# Copy_of_ST_LINK_V2-1.net
KiCad netlist of a schematic drawn in Altium Designer
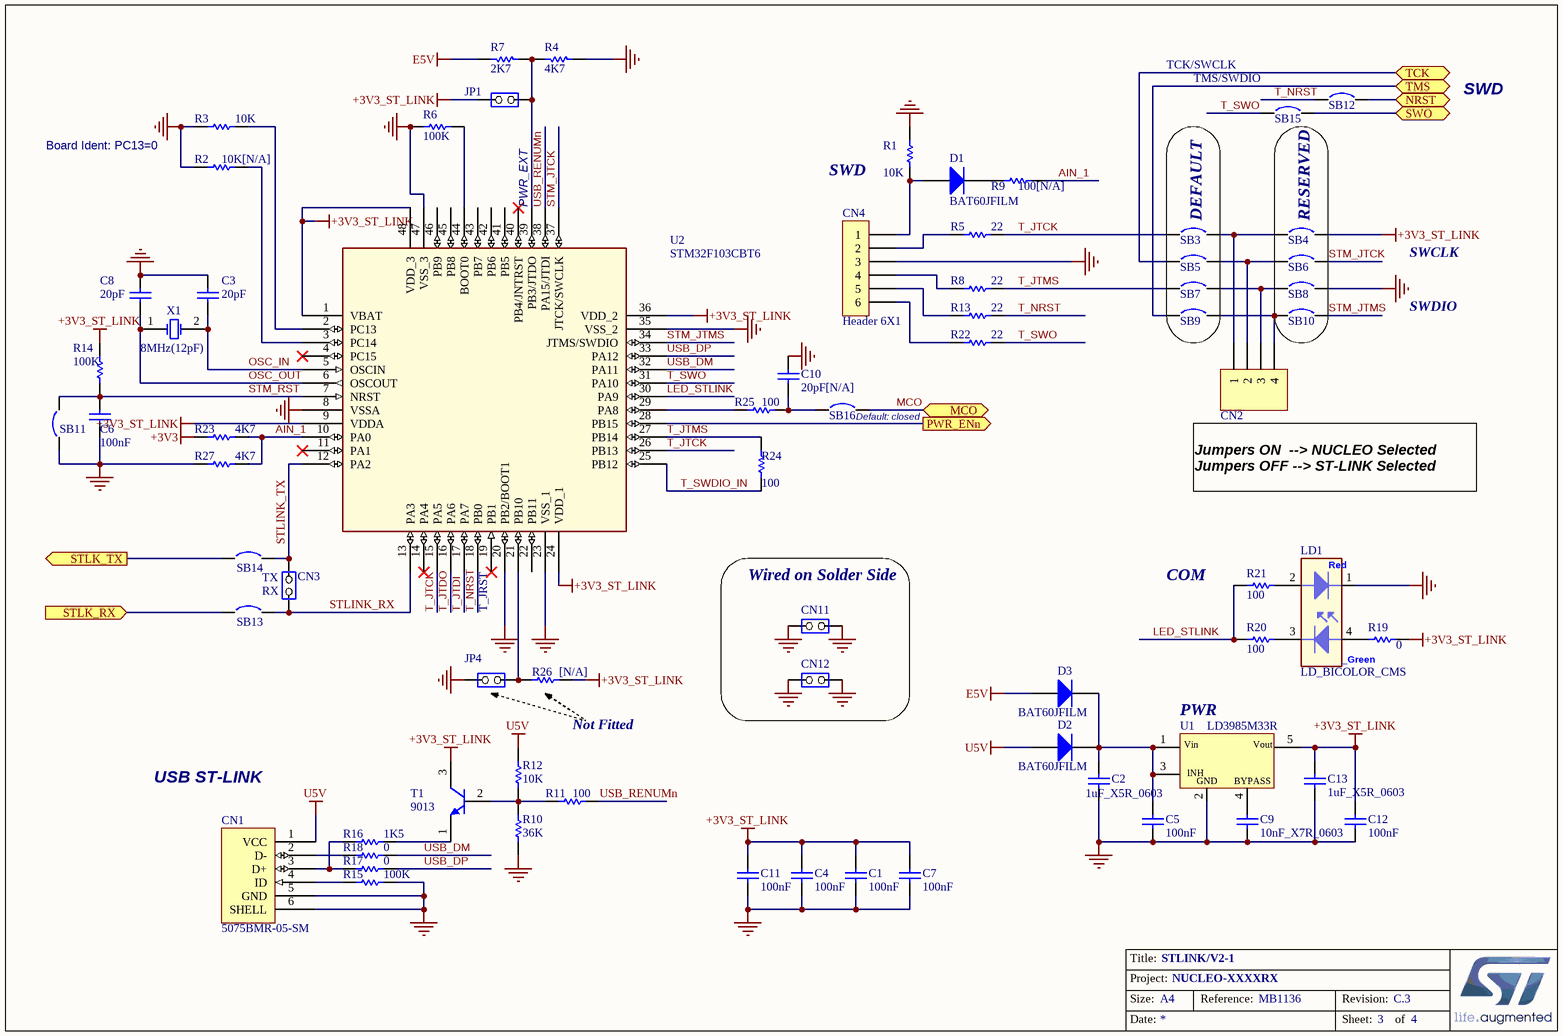
[diagram p0: Copy of ST_LINK_V2-1.SCHDOC]

(export (version "E")
  (design (tool "Eeschema 10.0.6"))
  (components
    (comp (ref "C1")
      (value "100nF")
      (footprint "0603C")
      (description "Capacitor 0402 / 0603 / 0805")
      (libsource (lib "MCD_TOOLS") (part "Capacitor_ST"))
    )
    (comp (ref "C2")
      (value "1uF_X5R_0603")
      (footprint "0603C")
      (description "0603  X5R 1µF")
      (fields (field (name "TOLERANCE") "10%"))
      (libsource (lib "MB963_1") (part "CAP SMD 0603  X5R 1µF 25V 10%"))
    )
    (comp (ref "C3")
      (value "20pF")
      (footprint "0603C")
      (description "Capacitor 0402 / 0603 / 0805")
      (libsource (lib "MCD_TOOLS") (part "Capacitor_ST"))
    )
    (comp (ref "C4")
      (value "100nF")
      (footprint "0603C")
      (description "Capacitor 0402 / 0603 / 0805")
      (libsource (lib "MCD_TOOLS") (part "Capacitor_ST"))
    )
    (comp (ref "C5")
      (value "100nF")
      (footprint "0603C")
      (description "Capacitor 0402 / 0603 / 0805")
      (libsource (lib "MCD_TOOLS") (part "Capacitor_ST"))
    )
    (comp (ref "C6")
      (value "100nF")
      (footprint "0603C")
      (description "Capacitor 0402 / 0603 / 0805")
      (libsource (lib "MCD_TOOLS") (part "Capacitor_ST"))
    )
    (comp (ref "C7")
      (value "100nF")
      (footprint "0603C")
      (description "Capacitor 0402 / 0603 / 0805")
      (libsource (lib "MCD_TOOLS") (part "Capacitor_ST"))
    )
    (comp (ref "C8")
      (value "20pF")
      (footprint "0603C")
      (description "Capacitor 0402 / 0603 / 0805")
      (libsource (lib "MCD_TOOLS") (part "Capacitor_ST"))
    )
    (comp (ref "C9")
      (value "10nF_X7R_0603")
      (footprint "0603C")
      (description "0603  X7R 10NF")
      (fields (field (name "TOLERANCE") "10%"))
      (libsource (lib "MB963_1") (part "CAP SMD 0603  X7R 10000PF 50V 10%"))
    )
    (comp (ref "C10")
      (value "20pF[N/A]")
      (footprint "0603C")
      (description "Capacitor 0402 / 0603 / 0805")
      (libsource (lib "MCD_TOOLS") (part "Capacitor_ST"))
    )
    (comp (ref "C11")
      (value "100nF")
      (footprint "0603C")
      (description "Capacitor 0402 / 0603 / 0805")
      (libsource (lib "MCD_TOOLS") (part "Capacitor_ST"))
    )
    (comp (ref "C12")
      (value "100nF")
      (footprint "0603C")
      (description "Capacitor 0402 / 0603 / 0805")
      (libsource (lib "MCD_TOOLS") (part "Capacitor_ST"))
    )
    (comp (ref "C13")
      (value "1uF_X5R_0603")
      (footprint "0603C")
      (description "0603  X5R 1µF")
      (fields (field (name "TOLERANCE") "10%"))
      (libsource (lib "MB963_1") (part "CAP SMD 0603  X5R 1µF 25V 10%"))
    )
    (comp (ref "CN1")
      (value "5075BMR-05-SM")
      (footprint "USB-MINI-B-SMD")
      (description "USB-MINI-typeB connector")
      (libsource (lib "MCD_TOOLS") (part "USB-MINI-typeB connector"))
    )
    (comp (ref "CN2")
      (value "Header 4")
      (footprint "1*4")
      (description "Header, 4-Pin, Single row")
      (fields (field (name "PUBLISHER") "Altium Limited"))
      (libsource (lib "Nucleo_64") (part "Header 4"))
    )
    (comp (ref "CN3") (value "~") (footprint "SIP2/2.54") (libsource (lib "MCD_TOOLS") (part "JP2")))
    (comp (ref "CN4")
      (value "Header 6X1")
      (footprint "1*6P")
      (description "Header, 6-Pin, Single row")
      (fields (field (name "PUBLISHER") "Altium Limited"))
      (libsource (lib "Nucleo_64") (part "Header 6X1"))
    )
    (comp (ref "CN11") (value "~") (footprint "SIP2/2.54") (libsource (lib "*") (part "JP2")))
    (comp (ref "CN12") (value "~") (footprint "SIP2/2.54") (libsource (lib "*") (part "JP2")))
    (comp (ref "D1")
      (value "BAT60JFILM")
      (footprint "SOD323/A")
      (libsource (lib "MCD_TOOLS") (part "BAT60JFILM"))
    )
    (comp (ref "D2")
      (value "BAT60JFILM")
      (footprint "SOD323/A")
      (libsource (lib "MCD_TOOLS") (part "BAT60JFILM"))
    )
    (comp (ref "D3")
      (value "BAT60JFILM")
      (footprint "SOD323/A")
      (libsource (lib "MCD_TOOLS") (part "BAT60JFILM"))
    )
    (comp (ref "JP1") (value "~") (footprint "SIP2/2.54") (libsource (lib "*") (part "JP2")))
    (comp (ref "JP4") (value "~") (footprint "SIP2/2.54") (libsource (lib "*") (part "JP2")))
    (comp (ref "LD1")
      (value "LD_BICOLOR_CMS")
      (footprint "HSMF-A201")
      (description "Bicolor Led")
      (libsource (lib "MCD_TOOLS") (part "LD_BICOLOR_CMS"))
    )
    (comp (ref "R1")
      (value "10K")
      (footprint "0603R")
      (description "Resistor 0402 or 0603 or 0805")
      (libsource (lib "Miscellaneous Devices") (part "Res1"))
    )
    (comp (ref "R2")
      (value "10K[N/A]")
      (footprint "0603R")
      (description "Resistor 0402 or 0603 or 0805")
      (libsource (lib "Miscellaneous Devices") (part "Res1"))
    )
    (comp (ref "R3")
      (value "10K")
      (footprint "0603R")
      (description "Resistor 0402 or 0603 or 0805")
      (libsource (lib "Miscellaneous Devices") (part "Res1"))
    )
    (comp (ref "R4")
      (value "4K7")
      (footprint "0603R")
      (description "Resistor")
      (fields (field (name "PUBLISHER") "Altium Limited"))
      (libsource (lib "") (part "Res1_2"))
    )
    (comp (ref "R5")
      (value "22")
      (footprint "0603R")
      (description "Resistor 0402 or 0603 or 0805")
      (libsource (lib "Miscellaneous Devices") (part "Res1"))
    )
    (comp (ref "R6")
      (value "100K")
      (footprint "0603R")
      (description "Resistor 0402 or 0603 or 0805")
      (libsource (lib "Miscellaneous Devices") (part "Res1"))
    )
    (comp (ref "R7")
      (value "2K7")
      (footprint "0603R")
      (description "Resistor")
      (fields (field (name "PUBLISHER") "Altium Limited"))
      (libsource (lib "") (part "Res1_2"))
    )
    (comp (ref "R8")
      (value "22")
      (footprint "0603R")
      (description "Resistor 0402 or 0603 or 0805")
      (libsource (lib "Miscellaneous Devices") (part "Res1"))
    )
    (comp (ref "R9")
      (value "100[N/A]")
      (footprint "0603R")
      (description "Resistor 0402 or 0603 or 0805")
      (libsource (lib "Miscellaneous Devices") (part "Res1"))
    )
    (comp (ref "R10")
      (value "36K")
      (footprint "0603R")
      (description "Resistor")
      (fields (field (name "PUBLISHER") "Altium Limited"))
      (libsource (lib "") (part "Res1_1"))
    )
    (comp (ref "R11")
      (value "100")
      (footprint "0603R")
      (description "Resistor 0402 or 0603 or 0805")
      (libsource (lib "Miscellaneous Devices") (part "Res1"))
    )
    (comp (ref "R12")
      (value "10K")
      (footprint "0603R")
      (description "Resistor")
      (fields (field (name "PUBLISHER") "Altium Limited"))
      (libsource (lib "") (part "Res1_1"))
    )
    (comp (ref "R13")
      (value "22")
      (footprint "0603R")
      (description "Resistor 0402 or 0603 or 0805")
      (libsource (lib "Miscellaneous Devices") (part "Res1"))
    )
    (comp (ref "R14")
      (value "100K")
      (footprint "0603R")
      (description "Resistor 0402 or 0603 or 0805")
      (libsource (lib "Miscellaneous Devices") (part "Res1"))
    )
    (comp (ref "R15")
      (value "100K")
      (footprint "0603R")
      (description "Resistor 0402 or 0603 or 0805")
      (libsource (lib "Miscellaneous Devices") (part "Res1"))
    )
    (comp (ref "R16")
      (value "1K5")
      (footprint "0603R")
      (description "Resistor 0402 or 0603 or 0805")
      (libsource (lib "Miscellaneous Devices") (part "Res1"))
    )
    (comp (ref "R17")
      (value "0")
      (footprint "0603R")
      (description "Resistor 0402 or 0603 or 0805")
      (libsource (lib "Miscellaneous Devices") (part "Res1"))
    )
    (comp (ref "R18")
      (value "0")
      (footprint "0603R")
      (description "Resistor 0402 or 0603 or 0805")
      (libsource (lib "Miscellaneous Devices") (part "Res1"))
    )
    (comp (ref "R19")
      (value "0")
      (footprint "0603R")
      (description "Resistor 0402 or 0603 or 0805")
      (libsource (lib "Miscellaneous Devices") (part "Res1"))
    )
    (comp (ref "R20")
      (value "100")
      (footprint "0603R")
      (description "Resistor 0402 or 0603 or 0805")
      (libsource (lib "Miscellaneous Devices") (part "Res1"))
    )
    (comp (ref "R21")
      (value "100")
      (footprint "0603R")
      (description "Resistor 0402 or 0603 or 0805")
      (libsource (lib "Miscellaneous Devices") (part "Res1"))
    )
    (comp (ref "R22")
      (value "22")
      (footprint "0603R")
      (description "Resistor 0402 or 0603 or 0805")
      (libsource (lib "Miscellaneous Devices") (part "Res1"))
    )
    (comp (ref "R23")
      (value "4K7")
      (footprint "0603R")
      (description "Resistor 0402 or 0603 or 0805")
      (libsource (lib "Miscellaneous Devices") (part "Res1"))
    )
    (comp (ref "R24")
      (value "100")
      (footprint "0603R")
      (description "Resistor 0402 or 0603 or 0805")
      (libsource (lib "Miscellaneous Devices") (part "Res1"))
    )
    (comp (ref "R25")
      (value "100")
      (footprint "0603R")
      (description "Resistor 0402 or 0603 or 0805")
      (libsource (lib "Miscellaneous Devices") (part "Res1"))
    )
    (comp (ref "R26")
      (value "[N/A]")
      (footprint "0603R")
      (description "Resistor")
      (fields (field (name "PUBLISHER") "Altium Limited"))
      (libsource (lib "") (part "Res1_1"))
    )
    (comp (ref "R27")
      (value "4K7")
      (footprint "0603R")
      (description "Resistor 0402 or 0603 or 0805")
      (libsource (lib "Miscellaneous Devices") (part "Res1"))
    )
    (comp (ref "SB3")
      (value "Circuit Breaker")
      (footprint "JP2_SMD")
      (fields (field (name "PUBLISHER") "Altium Limited"))
      (libsource (lib "MB915") (part "Circuit Breaker"))
    )
    (comp (ref "SB4")
      (value "Circuit Breaker")
      (footprint "JP2_SMD")
      (fields (field (name "PUBLISHER") "Altium Limited"))
      (libsource (lib "MB915") (part "Circuit Breaker"))
    )
    (comp (ref "SB5")
      (value "Circuit Breaker")
      (footprint "JP2_SMD")
      (fields (field (name "PUBLISHER") "Altium Limited"))
      (libsource (lib "MB915") (part "Circuit Breaker"))
    )
    (comp (ref "SB6")
      (value "Circuit Breaker")
      (footprint "JP2_SMD")
      (fields (field (name "PUBLISHER") "Altium Limited"))
      (libsource (lib "MB915") (part "Circuit Breaker"))
    )
    (comp (ref "SB7")
      (value "Circuit Breaker")
      (footprint "JP2_SMD")
      (fields (field (name "PUBLISHER") "Altium Limited"))
      (libsource (lib "MB915") (part "Circuit Breaker"))
    )
    (comp (ref "SB8")
      (value "Circuit Breaker")
      (footprint "JP2_SMD")
      (fields (field (name "PUBLISHER") "Altium Limited"))
      (libsource (lib "MB915") (part "Circuit Breaker"))
    )
    (comp (ref "SB9")
      (value "Circuit Breaker")
      (footprint "JP2_SMD")
      (fields (field (name "PUBLISHER") "Altium Limited"))
      (libsource (lib "MB915") (part "Circuit Breaker"))
    )
    (comp (ref "SB10")
      (value "Circuit Breaker")
      (footprint "JP2_SMD")
      (fields (field (name "PUBLISHER") "Altium Limited"))
      (libsource (lib "MB915") (part "Circuit Breaker"))
    )
    (comp (ref "SB11")
      (value "Circuit Breaker")
      (footprint "JP2_SMD")
      (fields (field (name "PUBLISHER") "Altium Limited"))
      (libsource (lib "MB915") (part "Circuit Breaker"))
    )
    (comp (ref "SB12")
      (value "Circuit Breaker")
      (footprint "JP2_SMD")
      (fields (field (name "PUBLISHER") "Altium Limited"))
      (libsource (lib "MB915") (part "Circuit Breaker"))
    )
    (comp (ref "SB13")
      (value "Circuit Breaker")
      (footprint "JP2_SMD")
      (fields (field (name "PUBLISHER") "Altium Limited"))
      (libsource (lib "MCD_TOOLS") (part "Circuit Breaker"))
    )
    (comp (ref "SB14")
      (value "Circuit Breaker")
      (footprint "JP2_SMD")
      (fields (field (name "PUBLISHER") "Altium Limited"))
      (libsource (lib "MCD_TOOLS") (part "Circuit Breaker"))
    )
    (comp (ref "SB15")
      (value "Circuit Breaker")
      (footprint "JP2_SMD")
      (fields (field (name "PUBLISHER") "Altium Limited"))
      (libsource (lib "MCD_TOOLS") (part "Circuit Breaker"))
    )
    (comp (ref "SB16")
      (value "Circuit Breaker")
      (footprint "JP2_SMD")
      (fields (field (name "PUBLISHER") "Altium Limited"))
      (libsource (lib "MCD_TOOLS") (part "Circuit Breaker"))
    )
    (comp (ref "T1")
      (value "9013")
      (footprint "SOT-23")
      (description "NPN Bipolar Transistor")
      (fields (field (name "PUBLISHER") "Altium Limited"))
      (libsource (lib "Miscellaneous Devices") (part "NPN"))
    )
    (comp (ref "U1")
      (value "LD3985M33R")
      (footprint "SOT-23-5L")
      (description "Ultra low drop-low noise BiCMOS voltage, regulators low ESR capacitors compatible")
      (libsource (lib "MCD_TOOLS") (part "LD3985M33R"))
    )
    (comp (ref "U2")
      (value "STM32F103CBT6")
      (footprint "QFP48 7X7")
      (description "Medium-density performance line ARM-based 32-bit MCU with 64KB Flash")
      (libsource (lib "Nucleo_64") (part "STM32F103CBT6"))
    )
    (comp (ref "X1")
      (value "8MHz(12pF)")
      (footprint "XTAL1")
      (description "Crystal Oscillator")
      (fields (field (name "PUBLISHER") "Altium Limited"))
      (libsource (lib "MB963_1") (part "XTAL"))
    )
  )
  (nets
    (net (code "1") (name "+3V3") (class "Default")
      (node (ref "R23") (pin "1") (pinfunction "1_1") (pintype "passive"))
    )
    (net (code "2") (name "+3V3_ST_LINK") (class "Default")
      (node (ref "C1") (pin "2") (pinfunction "2_2") (pintype "passive"))
      (node (ref "C11") (pin "2") (pinfunction "2_2") (pintype "passive"))
      (node (ref "C12") (pin "2") (pinfunction "2_2") (pintype "passive"))
      (node (ref "C13") (pin "1") (pinfunction "1_1") (pintype "passive"))
      (node (ref "C4") (pin "2") (pinfunction "2_2") (pintype "passive"))
      (node (ref "C7") (pin "2") (pinfunction "2_2") (pintype "passive"))
      (node (ref "JP1") (pin "1") (pinfunction "COMMON_1") (pintype "passive"))
      (node (ref "R14") (pin "2") (pinfunction "2_2") (pintype "passive"))
      (node (ref "R19") (pin "2") (pinfunction "2_2") (pintype "passive"))
      (node (ref "R26") (pin "1") (pinfunction "1_1") (pintype "passive"))
      (node (ref "SB4") (pin "2") (pinfunction "2_2") (pintype "passive"))
      (node (ref "T1") (pin "3") (pinfunction "C_3") (pintype "passive"))
      (node (ref "U1") (pin "5") (pinfunction "Vout_5") (pintype "passive"))
      (node (ref "U2") (pin "1") (pinfunction "VBAT_1") (pintype "power_in"))
      (node (ref "U2") (pin "24") (pinfunction "VDD_1_24") (pintype "power_in"))
      (node (ref "U2") (pin "36") (pinfunction "VDD_2_36") (pintype "power_in"))
      (node (ref "U2") (pin "48") (pinfunction "VDD_3_48") (pintype "power_in"))
      (node (ref "U2") (pin "9") (pinfunction "VDDA_9") (pintype "power_in"))
    )
    (net (code "3") (name "/AIN_1") (class "Default")
      (node (ref "R23") (pin "2") (pinfunction "2_2") (pintype "passive"))
      (node (ref "R27") (pin "2") (pinfunction "2_2") (pintype "passive"))
      (node (ref "R9") (pin "2") (pinfunction "2_2") (pintype "passive"))
      (node (ref "U2") (pin "10") (pinfunction "PA0_10") (pintype "bidirectional"))
    )
    (net (code "4") (name "/LED_STLINK") (class "Default")
      (node (ref "R20") (pin "1") (pinfunction "1_1") (pintype "passive"))
      (node (ref "R21") (pin "1") (pinfunction "1_1") (pintype "passive"))
      (node (ref "U2") (pin "30") (pinfunction "PA9_30") (pintype "bidirectional"))
    )
    (net (code "5") (name "/MCO") (class "Default")
      (node (ref "SB16") (pin "2") (pinfunction "2_2") (pintype "passive"))
    )
    (net (code "6") (name "/NRST") (class "Default")
      (node (ref "SB12") (pin "2") (pinfunction "2_2") (pintype "passive"))
    )
    (net (code "7") (name "/OSC_IN") (class "Default")
      (node (ref "C3") (pin "1") (pinfunction "1_1") (pintype "passive"))
      (node (ref "U2") (pin "5") (pinfunction "OSCIN_5") (pintype "input"))
      (node (ref "X1") (pin "2") (pinfunction "OSC2_2") (pintype "passive"))
    )
    (net (code "8") (name "/OSC_OUT") (class "Default")
      (node (ref "C8") (pin "1") (pinfunction "1_1") (pintype "passive"))
      (node (ref "U2") (pin "6") (pinfunction "OSCOUT_6") (pintype "output"))
      (node (ref "X1") (pin "1") (pinfunction "OSC1_1") (pintype "passive"))
    )
    (net (code "9") (name "/PWR_ENn") (class "Default")
      (node (ref "U2") (pin "28") (pinfunction "PB15_28") (pintype "bidirectional"))
    )
    (net (code "10") (name "/STLINK_RX") (class "Default")
      (node (ref "CN3") (pin "1") (pinfunction "COMMON_1") (pintype "passive"))
      (node (ref "SB13") (pin "2") (pinfunction "2_2") (pintype "passive"))
      (node (ref "U2") (pin "13") (pinfunction "PA3_13") (pintype "bidirectional"))
    )
    (net (code "11") (name "/STLINK_TX") (class "Default")
      (node (ref "CN3") (pin "2") (pinfunction "NO_2") (pintype "passive"))
      (node (ref "SB14") (pin "2") (pinfunction "2_2") (pintype "passive"))
      (node (ref "U2") (pin "12") (pinfunction "PA2_12") (pintype "bidirectional"))
    )
    (net (code "12") (name "/STLK_RX") (class "Default")
      (node (ref "SB13") (pin "1") (pinfunction "1_1") (pintype "passive"))
    )
    (net (code "13") (name "/STLK_TX") (class "Default")
      (node (ref "SB14") (pin "1") (pinfunction "1_1") (pintype "passive"))
    )
    (net (code "14") (name "/STM_JTCK") (class "Default")
      (node (ref "SB6") (pin "2") (pinfunction "2_2") (pintype "passive"))
      (node (ref "U2") (pin "37") (pinfunction "JTCK/SWCLK_37") (pintype "bidirectional"))
    )
    (net (code "15") (name "/STM_JTMS") (class "Default")
      (node (ref "SB10") (pin "2") (pinfunction "2_2") (pintype "passive"))
      (node (ref "U2") (pin "34") (pinfunction "JTMS/SWDIO_34") (pintype "bidirectional"))
    )
    (net (code "16") (name "/STM_RST") (class "Default")
      (node (ref "C6") (pin "2") (pinfunction "2_2") (pintype "passive"))
      (node (ref "R14") (pin "1") (pinfunction "1_1") (pintype "passive"))
      (node (ref "SB11") (pin "2") (pinfunction "2_2") (pintype "passive"))
      (node (ref "U2") (pin "7") (pinfunction "NRST_7") (pintype "input"))
    )
    (net (code "17") (name "/SWO") (class "Default")
      (node (ref "SB15") (pin "2") (pinfunction "2_2") (pintype "passive"))
    )
    (net (code "18") (name "/TCK") (class "Default")
      (node (ref "SB5") (pin "1") (pinfunction "1_1") (pintype "passive"))
    )
    (net (code "19") (name "/TMS") (class "Default")
      (node (ref "SB9") (pin "1") (pinfunction "1_1") (pintype "passive"))
    )
    (net (code "20") (name "/T_JTCK") (class "Default")
      (node (ref "R5") (pin "2") (pinfunction "2_2") (pintype "passive"))
      (node (ref "SB3") (pin "1") (pinfunction "1_1") (pintype "passive"))
      (node (ref "U2") (pin "15") (pinfunction "PA5_15") (pintype "bidirectional"))
      (node (ref "U2") (pin "26") (pinfunction "PB13_26") (pintype "bidirectional"))
    )
    (net (code "21") (name "/T_JTDI") (class "Default")
      (node (ref "U2") (pin "17") (pinfunction "PA7_17") (pintype "bidirectional"))
    )
    (net (code "22") (name "/T_JTDO") (class "Default")
      (node (ref "U2") (pin "16") (pinfunction "PA6_16") (pintype "bidirectional"))
    )
    (net (code "23") (name "/T_JTMS") (class "Default")
      (node (ref "R24") (pin "2") (pinfunction "2_2") (pintype "passive"))
      (node (ref "R8") (pin "2") (pinfunction "2_2") (pintype "passive"))
      (node (ref "SB7") (pin "1") (pinfunction "1_1") (pintype "passive"))
      (node (ref "U2") (pin "27") (pinfunction "PB14_27") (pintype "bidirectional"))
    )
    (net (code "24") (name "/T_NRST") (class "Default")
      (node (ref "R13") (pin "2") (pinfunction "2_2") (pintype "passive"))
      (node (ref "SB12") (pin "1") (pinfunction "1_1") (pintype "passive"))
      (node (ref "U2") (pin "18") (pinfunction "PB0_18") (pintype "bidirectional"))
    )
    (net (code "25") (name "/T_SWDIO_IN") (class "Default")
      (node (ref "R24") (pin "1") (pinfunction "1_1") (pintype "passive"))
      (node (ref "U2") (pin "25") (pinfunction "PB12_25") (pintype "bidirectional"))
    )
    (net (code "26") (name "/T_SWO") (class "Default")
      (node (ref "R22") (pin "2") (pinfunction "2_2") (pintype "passive"))
      (node (ref "SB15") (pin "1") (pinfunction "1_1") (pintype "passive"))
      (node (ref "U2") (pin "31") (pinfunction "PA10_31") (pintype "bidirectional"))
    )
    (net (code "27") (name "/USB_DM") (class "Default")
      (node (ref "R18") (pin "2") (pinfunction "2_2") (pintype "passive"))
      (node (ref "U2") (pin "32") (pinfunction "PA11_32") (pintype "bidirectional"))
    )
    (net (code "28") (name "/USB_DP") (class "Default")
      (node (ref "R17") (pin "2") (pinfunction "2_2") (pintype "passive"))
      (node (ref "U2") (pin "33") (pinfunction "PA12_33") (pintype "bidirectional"))
    )
    (net (code "29") (name "/USB_RENUMn") (class "Default")
      (node (ref "R11") (pin "2") (pinfunction "2_2") (pintype "passive"))
      (node (ref "U2") (pin "38") (pinfunction "PA15/JTDI_38") (pintype "bidirectional"))
    )
    (net (code "30") (name "E5V") (class "Default")
      (node (ref "D3") (pin "1") (pinfunction "A_1") (pintype "passive"))
      (node (ref "R7") (pin "1") (pinfunction "1_1") (pintype "passive"))
    )
    (net (code "31") (name "GND") (class "Default")
      (node (ref "C1") (pin "1") (pinfunction "1_1") (pintype "passive"))
      (node (ref "C10") (pin "2") (pinfunction "2_2") (pintype "passive"))
      (node (ref "C11") (pin "1") (pinfunction "1_1") (pintype "passive"))
      (node (ref "C12") (pin "1") (pinfunction "1_1") (pintype "passive"))
      (node (ref "C13") (pin "2") (pinfunction "2_2") (pintype "passive"))
      (node (ref "C2") (pin "1") (pinfunction "1_1") (pintype "passive"))
      (node (ref "C3") (pin "2") (pinfunction "2_2") (pintype "passive"))
      (node (ref "C4") (pin "1") (pinfunction "1_1") (pintype "passive"))
      (node (ref "C5") (pin "1") (pinfunction "1_1") (pintype "passive"))
      (node (ref "C6") (pin "1") (pinfunction "1_1") (pintype "passive"))
      (node (ref "C7") (pin "1") (pinfunction "1_1") (pintype "passive"))
      (node (ref "C8") (pin "2") (pinfunction "2_2") (pintype "passive"))
      (node (ref "C9") (pin "1") (pinfunction "1_1") (pintype "passive"))
      (node (ref "CN1") (pin "5") (pinfunction "GND_5") (pintype "power_in"))
      (node (ref "CN1") (pin "6") (pinfunction "SHELL_6") (pintype "power_in"))
      (node (ref "CN11") (pin "1") (pinfunction "COMMON_1") (pintype "passive"))
      (node (ref "CN11") (pin "2") (pinfunction "NO_2") (pintype "passive"))
      (node (ref "CN12") (pin "1") (pinfunction "COMMON_1") (pintype "passive"))
      (node (ref "CN12") (pin "2") (pinfunction "NO_2") (pintype "passive"))
      (node (ref "CN4") (pin "3") (pinfunction "3_3") (pintype "passive"))
      (node (ref "JP4") (pin "1") (pinfunction "COMMON_1") (pintype "passive"))
      (node (ref "LD1") (pin "1") (pinfunction "1_1") (pintype "passive"))
      (node (ref "R1") (pin "2") (pinfunction "2_2") (pintype "passive"))
      (node (ref "R10") (pin "1") (pinfunction "1_1") (pintype "passive"))
      (node (ref "R15") (pin "2") (pinfunction "2_2") (pintype "passive"))
      (node (ref "R2") (pin "1") (pinfunction "1_1") (pintype "passive"))
      (node (ref "R27") (pin "1") (pinfunction "1_1") (pintype "passive"))
      (node (ref "R3") (pin "1") (pinfunction "1_1") (pintype "passive"))
      (node (ref "R4") (pin "2") (pinfunction "2_2") (pintype "passive"))
      (node (ref "R6") (pin "1") (pinfunction "1_1") (pintype "passive"))
      (node (ref "SB11") (pin "1") (pinfunction "1_1") (pintype "passive"))
      (node (ref "SB8") (pin "2") (pinfunction "2_2") (pintype "passive"))
      (node (ref "U1") (pin "2") (pinfunction "GND_2") (pintype "passive"))
      (node (ref "U2") (pin "20") (pinfunction "PB2/BOOT1_20") (pintype "bidirectional"))
      (node (ref "U2") (pin "23") (pinfunction "VSS_1_23") (pintype "power_in"))
      (node (ref "U2") (pin "35") (pinfunction "VSS_2_35") (pintype "power_in"))
      (node (ref "U2") (pin "47") (pinfunction "VSS_3_47") (pintype "power_in"))
      (node (ref "U2") (pin "8") (pinfunction "VSSA_8") (pintype "power_in"))
    )
    (net (code "32") (name "Net-(C10-Pad1)") (class "Default")
      (node (ref "C10") (pin "1") (pinfunction "1_1") (pintype "passive"))
      (node (ref "R25") (pin "2") (pinfunction "2_2") (pintype "passive"))
      (node (ref "SB16") (pin "1") (pinfunction "1_1") (pintype "passive"))
    )
    (net (code "33") (name "Net-(CN1-D+)") (class "Default")
      (node (ref "CN1") (pin "3") (pinfunction "D+_3") (pintype "bidirectional"))
      (node (ref "R16") (pin "1") (pinfunction "1_1") (pintype "passive"))
      (node (ref "R17") (pin "1") (pinfunction "1_1") (pintype "passive"))
    )
    (net (code "34") (name "Net-(CN1-D-)") (class "Default")
      (node (ref "CN1") (pin "2") (pinfunction "D-_2") (pintype "bidirectional"))
      (node (ref "R18") (pin "1") (pinfunction "1_1") (pintype "passive"))
    )
    (net (code "35") (name "Net-(CN1-ID)") (class "Default")
      (node (ref "CN1") (pin "4") (pinfunction "ID_4") (pintype "input"))
      (node (ref "R15") (pin "1") (pinfunction "1_1") (pintype "passive"))
    )
    (net (code "36") (name "Net-(CN2-Pad1)") (class "Default")
      (node (ref "CN2") (pin "1") (pinfunction "1_1") (pintype "passive"))
      (node (ref "SB3") (pin "2") (pinfunction "2_2") (pintype "passive"))
      (node (ref "SB4") (pin "1") (pinfunction "1_1") (pintype "passive"))
    )
    (net (code "37") (name "Net-(CN2-Pad2)") (class "Default")
      (node (ref "CN2") (pin "2") (pinfunction "2_2") (pintype "passive"))
      (node (ref "SB5") (pin "2") (pinfunction "2_2") (pintype "passive"))
      (node (ref "SB6") (pin "1") (pinfunction "1_1") (pintype "passive"))
    )
    (net (code "38") (name "Net-(CN2-Pad3)") (class "Default")
      (node (ref "CN2") (pin "3") (pinfunction "3_3") (pintype "passive"))
      (node (ref "SB7") (pin "2") (pinfunction "2_2") (pintype "passive"))
      (node (ref "SB8") (pin "1") (pinfunction "1_1") (pintype "passive"))
    )
    (net (code "39") (name "Net-(CN2-Pad4)") (class "Default")
      (node (ref "CN2") (pin "4") (pinfunction "4_4") (pintype "passive"))
      (node (ref "SB10") (pin "1") (pinfunction "1_1") (pintype "passive"))
      (node (ref "SB9") (pin "2") (pinfunction "2_2") (pintype "passive"))
    )
    (net (code "40") (name "Net-(CN4-Pad2)") (class "Default")
      (node (ref "CN4") (pin "2") (pinfunction "2_2") (pintype "passive"))
      (node (ref "R5") (pin "1") (pinfunction "1_1") (pintype "passive"))
    )
    (net (code "41") (name "Net-(CN4-Pad4)") (class "Default")
      (node (ref "CN4") (pin "4") (pinfunction "4_4") (pintype "passive"))
      (node (ref "R8") (pin "1") (pinfunction "1_1") (pintype "passive"))
    )
    (net (code "42") (name "Net-(CN4-Pad5)") (class "Default")
      (node (ref "CN4") (pin "5") (pinfunction "5_5") (pintype "passive"))
      (node (ref "R13") (pin "1") (pinfunction "1_1") (pintype "passive"))
    )
    (net (code "43") (name "Net-(CN4-Pad6)") (class "Default")
      (node (ref "CN4") (pin "6") (pinfunction "6_6") (pintype "passive"))
      (node (ref "R22") (pin "1") (pinfunction "1_1") (pintype "passive"))
    )
    (net (code "44") (name "Net-(D1-A)") (class "Default")
      (node (ref "CN4") (pin "1") (pinfunction "1_1") (pintype "passive"))
      (node (ref "D1") (pin "1") (pinfunction "A_1") (pintype "passive"))
      (node (ref "R1") (pin "1") (pinfunction "1_1") (pintype "passive"))
    )
    (net (code "45") (name "Net-(D1-K)") (class "Default")
      (node (ref "D1") (pin "2") (pinfunction "K_2") (pintype "passive"))
      (node (ref "R9") (pin "1") (pinfunction "1_1") (pintype "passive"))
    )
    (net (code "46") (name "Net-(D2-K)") (class "Default")
      (node (ref "C2") (pin "2") (pinfunction "2_2") (pintype "passive"))
      (node (ref "C5") (pin "2") (pinfunction "2_2") (pintype "passive"))
      (node (ref "D2") (pin "2") (pinfunction "K_2") (pintype "passive"))
      (node (ref "D3") (pin "2") (pinfunction "K_2") (pintype "passive"))
      (node (ref "U1") (pin "1") (pinfunction "Vin_1") (pintype "passive"))
      (node (ref "U1") (pin "3") (pinfunction "CE_3") (pintype "passive"))
    )
    (net (code "47") (name "Net-(JP1-NO)") (class "Default")
      (node (ref "JP1") (pin "2") (pinfunction "NO_2") (pintype "passive"))
      (node (ref "R4") (pin "1") (pinfunction "1_1") (pintype "passive"))
      (node (ref "R7") (pin "2") (pinfunction "2_2") (pintype "passive"))
      (node (ref "U2") (pin "39") (pinfunction "PB3/JTDO_39") (pintype "bidirectional"))
    )
    (net (code "48") (name "Net-(JP4-NO)") (class "Default")
      (node (ref "JP4") (pin "2") (pinfunction "NO_2") (pintype "passive"))
      (node (ref "R26") (pin "2") (pinfunction "2_2") (pintype "passive"))
      (node (ref "U2") (pin "21") (pinfunction "PB10_21") (pintype "bidirectional"))
    )
    (net (code "49") (name "Net-(LD1-Pad2)") (class "Default")
      (node (ref "LD1") (pin "2") (pinfunction "2_2") (pintype "passive"))
      (node (ref "R21") (pin "2") (pinfunction "2_2") (pintype "passive"))
    )
    (net (code "50") (name "Net-(LD1-Pad3)") (class "Default")
      (node (ref "LD1") (pin "3") (pinfunction "3_3") (pintype "passive"))
      (node (ref "R20") (pin "2") (pinfunction "2_2") (pintype "passive"))
    )
    (net (code "51") (name "Net-(LD1-Pad4)") (class "Default")
      (node (ref "LD1") (pin "4") (pinfunction "4_4") (pintype "passive"))
      (node (ref "R19") (pin "1") (pinfunction "1_1") (pintype "passive"))
    )
    (net (code "52") (name "Net-(T1-B)") (class "Default")
      (node (ref "R10") (pin "2") (pinfunction "2_2") (pintype "passive"))
      (node (ref "R11") (pin "1") (pinfunction "1_1") (pintype "passive"))
      (node (ref "R12") (pin "1") (pinfunction "1_1") (pintype "passive"))
      (node (ref "T1") (pin "2") (pinfunction "B_2") (pintype "passive"))
    )
    (net (code "53") (name "Net-(T1-E)") (class "Default")
      (node (ref "R16") (pin "2") (pinfunction "2_2") (pintype "passive"))
      (node (ref "T1") (pin "1") (pinfunction "E_1") (pintype "passive"))
    )
    (net (code "54") (name "Net-(U1-BYPASS)") (class "Default")
      (node (ref "C9") (pin "2") (pinfunction "2_2") (pintype "passive"))
      (node (ref "U1") (pin "4") (pinfunction "BYPASS_4") (pintype "passive"))
    )
    (net (code "55") (name "Net-(U2-BOOT0)") (class "Default")
      (node (ref "R6") (pin "2") (pinfunction "2_2") (pintype "passive"))
      (node (ref "U2") (pin "44") (pinfunction "BOOT0_44") (pintype "bidirectional"))
    )
    (net (code "56") (name "Net-(U2-PA8)") (class "Default")
      (node (ref "R25") (pin "1") (pinfunction "1_1") (pintype "passive"))
      (node (ref "U2") (pin "29") (pinfunction "PA8_29") (pintype "bidirectional"))
    )
    (net (code "57") (name "Net-(U2-PC13)") (class "Default")
      (node (ref "R3") (pin "2") (pinfunction "2_2") (pintype "passive"))
      (node (ref "U2") (pin "2") (pinfunction "PC13_2") (pintype "bidirectional"))
    )
    (net (code "58") (name "Net-(U2-PC14)") (class "Default")
      (node (ref "R2") (pin "2") (pinfunction "2_2") (pintype "passive"))
      (node (ref "U2") (pin "3") (pinfunction "PC14_3") (pintype "bidirectional"))
    )
    (net (code "59") (name "U5V") (class "Default")
      (node (ref "CN1") (pin "1") (pinfunction "VCC_1") (pintype "power_in"))
      (node (ref "D2") (pin "1") (pinfunction "A_1") (pintype "passive"))
      (node (ref "R12") (pin "2") (pinfunction "2_2") (pintype "passive"))
    )
    (net (code "60") (name "unconnected-(U2-PA1-Pad11)") (class "Default")
      (node (ref "U2") (pin "11") (pinfunction "PA1_11") (pintype "bidirectional+no_connect"))
    )
    (net (code "61") (name "unconnected-(U2-PA4-Pad14)") (class "Default")
      (node (ref "U2") (pin "14") (pinfunction "PA4_14") (pintype "bidirectional+no_connect"))
    )
    (net (code "62") (name "unconnected-(U2-PB1-Pad19)") (class "Default")
      (node (ref "U2") (pin "19") (pinfunction "PB1_19") (pintype "input+no_connect"))
    )
    (net (code "63") (name "unconnected-(U2-PB4{slash}JNTRST-Pad40)") (class "Default")
      (node (ref "U2") (pin "40") (pinfunction "PB4/JNTRST_40") (pintype "bidirectional+no_connect"))
    )
    (net (code "64") (name "unconnected-(U2-PB5-Pad41)") (class "Default")
      (node (ref "U2") (pin "41") (pinfunction "PB5_41") (pintype "bidirectional"))
    )
    (net (code "65") (name "unconnected-(U2-PB6-Pad42)") (class "Default")
      (node (ref "U2") (pin "42") (pinfunction "PB6_42") (pintype "bidirectional"))
    )
    (net (code "66") (name "unconnected-(U2-PB7-Pad43)") (class "Default")
      (node (ref "U2") (pin "43") (pinfunction "PB7_43") (pintype "bidirectional"))
    )
    (net (code "67") (name "unconnected-(U2-PB8-Pad45)") (class "Default")
      (node (ref "U2") (pin "45") (pinfunction "PB8_45") (pintype "bidirectional"))
    )
    (net (code "68") (name "unconnected-(U2-PB9-Pad46)") (class "Default")
      (node (ref "U2") (pin "46") (pinfunction "PB9_46") (pintype "bidirectional"))
    )
    (net (code "69") (name "unconnected-(U2-PB11-Pad22)") (class "Default")
      (node (ref "U2") (pin "22") (pinfunction "PB11_22") (pintype "bidirectional"))
    )
    (net (code "70") (name "unconnected-(U2-PC15-Pad4)") (class "Default")
      (node (ref "U2") (pin "4") (pinfunction "PC15_4") (pintype "bidirectional+no_connect"))
    )
  )
)
